# OSPLC2_2_CPU3.net
KiCad netlist of a schematic drawn in Altium Designer
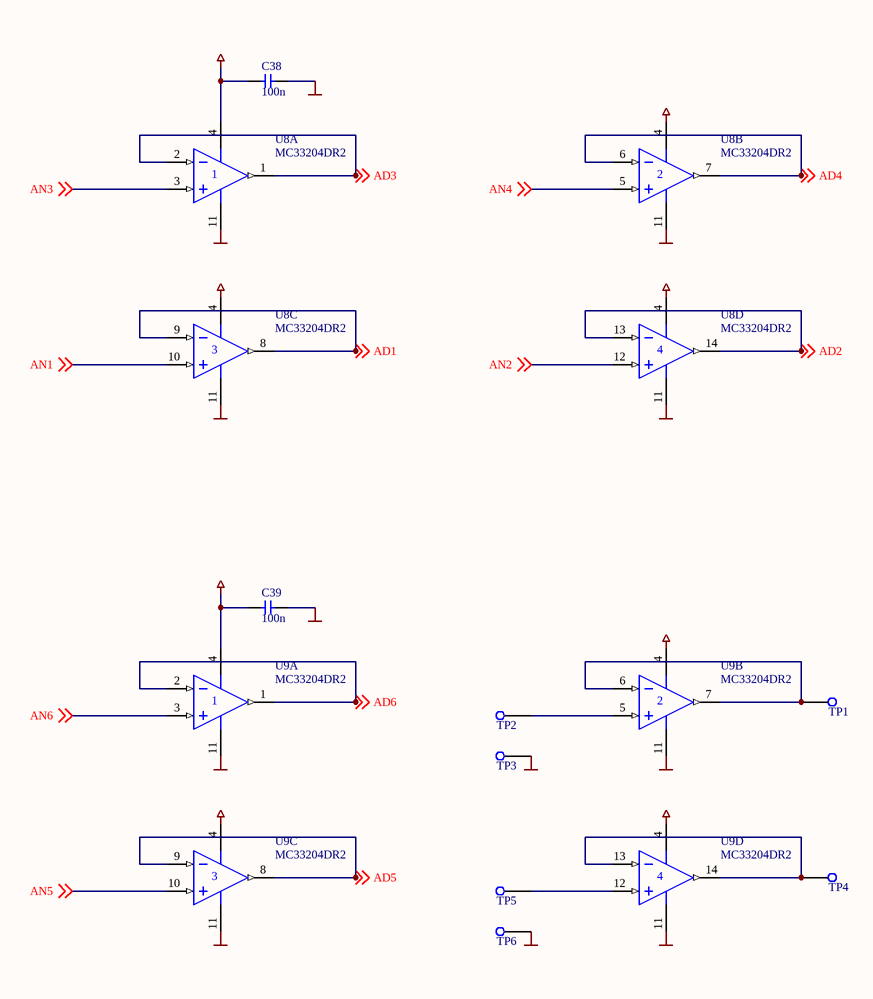
[diagram p0: OSPLC2_2_CPU3.SchDoc]

(export (version "E")
  (design (tool "Eeschema 10.0.6"))
  (components
    (comp (ref "C38")
      (value "0603")
      (footprint "0603")
      (description "0603 footprint non-polorised capacitor")
      (fields (field (name "ALTIUM_VALUE") "100n"))
      (libsource (lib "Integrated Comp_lib") (part "CAP_0603"))
    )
    (comp (ref "C39")
      (value "0603")
      (footprint "0603")
      (description "0603 footprint non-polorised capacitor")
      (fields (field (name "ALTIUM_VALUE") "100n"))
      (libsource (lib "Integrated Comp_lib") (part "CAP_0603"))
    )
    (comp (ref "TP1")
      (value "TEST POINT")
      (footprint "TEST_POINT_TH")
      (description "Through hole test point")
      (libsource (lib "ARM_projects") (part "TEST_POINT_TH"))
    )
    (comp (ref "TP2")
      (value "TEST POINT")
      (footprint "TEST_POINT_TH")
      (description "Through hole test point")
      (libsource (lib "ARM_projects") (part "TEST_POINT_TH"))
    )
    (comp (ref "TP3")
      (value "TEST POINT")
      (footprint "TEST_POINT_TH")
      (description "Through hole test point")
      (libsource (lib "ARM_projects") (part "TEST_POINT_TH"))
    )
    (comp (ref "TP4")
      (value "TEST POINT")
      (footprint "TEST_POINT_TH")
      (description "Through hole test point")
      (libsource (lib "ARM_projects") (part "TEST_POINT_TH"))
    )
    (comp (ref "TP5")
      (value "TEST POINT")
      (footprint "TEST_POINT_TH")
      (description "Through hole test point")
      (libsource (lib "ARM_projects") (part "TEST_POINT_TH"))
    )
    (comp (ref "TP6")
      (value "TEST POINT")
      (footprint "TEST_POINT_TH")
      (description "Through hole test point")
      (libsource (lib "ARM_projects") (part "TEST_POINT_TH"))
    )
    (comp (ref "U8")
      (value "MC33204DR2")
      (footprint "SO-G14")
      (description "Rail-to-Rail Quad Operational Amplifier")
      (fields (field (name "MANUFACTURER") "Motorola") (field (name "PUBLISHER") "Altium Limited"))
      (libsource (lib "Motorola Amplifier Operational Amplifier") (part "MC33204DR2"))
    )
    (comp (ref "U9")
      (value "MC33204DR2")
      (footprint "SO-G14")
      (description "Rail-to-Rail Quad Operational Amplifier")
      (fields (field (name "MANUFACTURER") "Motorola") (field (name "PUBLISHER") "Altium Limited"))
      (libsource (lib "Motorola Amplifier Operational Amplifier") (part "MC33204DR2"))
    )
  )
  (nets
    (net (code "1") (name "AD1") (class "Default")
      (node (ref "U8") (pin "8") (pinfunction "OUT_8") (pintype "output"))
      (node (ref "U8") (pin "9") (pinfunction "IN-_9") (pintype "input"))
    )
    (net (code "2") (name "AD2") (class "Default")
      (node (ref "U8") (pin "13") (pinfunction "IN-_13") (pintype "input"))
      (node (ref "U8") (pin "14") (pinfunction "OUT_14") (pintype "output"))
    )
    (net (code "3") (name "AD3") (class "Default")
      (node (ref "U8") (pin "1") (pinfunction "OUT_1") (pintype "output"))
      (node (ref "U8") (pin "2") (pinfunction "IN-_2") (pintype "input"))
    )
    (net (code "4") (name "AD4") (class "Default")
      (node (ref "U8") (pin "6") (pinfunction "IN-_6") (pintype "input"))
      (node (ref "U8") (pin "7") (pinfunction "OUT_7") (pintype "output"))
    )
    (net (code "5") (name "AD5") (class "Default")
      (node (ref "U9") (pin "8") (pinfunction "OUT_8") (pintype "output"))
      (node (ref "U9") (pin "9") (pinfunction "IN-_9") (pintype "input"))
    )
    (net (code "6") (name "AD6") (class "Default")
      (node (ref "U9") (pin "1") (pinfunction "OUT_1") (pintype "output"))
      (node (ref "U9") (pin "2") (pinfunction "IN-_2") (pintype "input"))
    )
    (net (code "7") (name "AN1") (class "Default")
      (node (ref "U8") (pin "10") (pinfunction "IN+_10") (pintype "input"))
    )
    (net (code "8") (name "AN2") (class "Default")
      (node (ref "U8") (pin "12") (pinfunction "IN+_12") (pintype "input"))
    )
    (net (code "9") (name "AN3") (class "Default")
      (node (ref "U8") (pin "3") (pinfunction "IN+_3") (pintype "input"))
    )
    (net (code "10") (name "AN4") (class "Default")
      (node (ref "U8") (pin "5") (pinfunction "IN+_5") (pintype "input"))
    )
    (net (code "11") (name "AN5") (class "Default")
      (node (ref "U9") (pin "10") (pinfunction "IN+_10") (pintype "input"))
    )
    (net (code "12") (name "AN6") (class "Default")
      (node (ref "U9") (pin "3") (pinfunction "IN+_3") (pintype "input"))
    )
    (net (code "13") (name "GND") (class "Default")
      (node (ref "C38") (pin "2") (pinfunction "2_2") (pintype "passive"))
      (node (ref "C39") (pin "2") (pinfunction "2_2") (pintype "passive"))
      (node (ref "TP3") (pin "1") (pinfunction "1_1") (pintype "passive"))
      (node (ref "TP6") (pin "1") (pinfunction "1_1") (pintype "passive"))
      (node (ref "U8") (pin "11") (pinfunction "V-_11") (pintype "power_in"))
      (node (ref "U9") (pin "11") (pinfunction "V-_11") (pintype "power_in"))
    )
    (net (code "14") (name "Net-(U9B-IN+)") (class "Default")
      (node (ref "TP2") (pin "1") (pinfunction "1_1") (pintype "passive"))
      (node (ref "U9") (pin "5") (pinfunction "IN+_5") (pintype "input"))
    )
    (net (code "15") (name "Net-(U9B-IN-)") (class "Default")
      (node (ref "TP1") (pin "1") (pinfunction "1_1") (pintype "passive"))
      (node (ref "U9") (pin "6") (pinfunction "IN-_6") (pintype "input"))
      (node (ref "U9") (pin "7") (pinfunction "OUT_7") (pintype "output"))
    )
    (net (code "16") (name "Net-(U9D-IN+)") (class "Default")
      (node (ref "TP5") (pin "1") (pinfunction "1_1") (pintype "passive"))
      (node (ref "U9") (pin "12") (pinfunction "IN+_12") (pintype "input"))
    )
    (net (code "17") (name "Net-(U9D-IN-)") (class "Default")
      (node (ref "TP4") (pin "1") (pinfunction "1_1") (pintype "passive"))
      (node (ref "U9") (pin "13") (pinfunction "IN-_13") (pintype "input"))
      (node (ref "U9") (pin "14") (pinfunction "OUT_14") (pintype "output"))
    )
    (net (code "18") (name "VCC3v3") (class "Default")
      (node (ref "C38") (pin "1") (pinfunction "1_1") (pintype "passive"))
      (node (ref "C39") (pin "1") (pinfunction "1_1") (pintype "passive"))
      (node (ref "U8") (pin "4") (pinfunction "V+_4") (pintype "power_in"))
      (node (ref "U9") (pin "4") (pinfunction "V+_4") (pintype "power_in"))
    )
  )
)
